# T5403_Barometer_Breakout.net
KiCad netlist of a schematic drawn in EAGLE
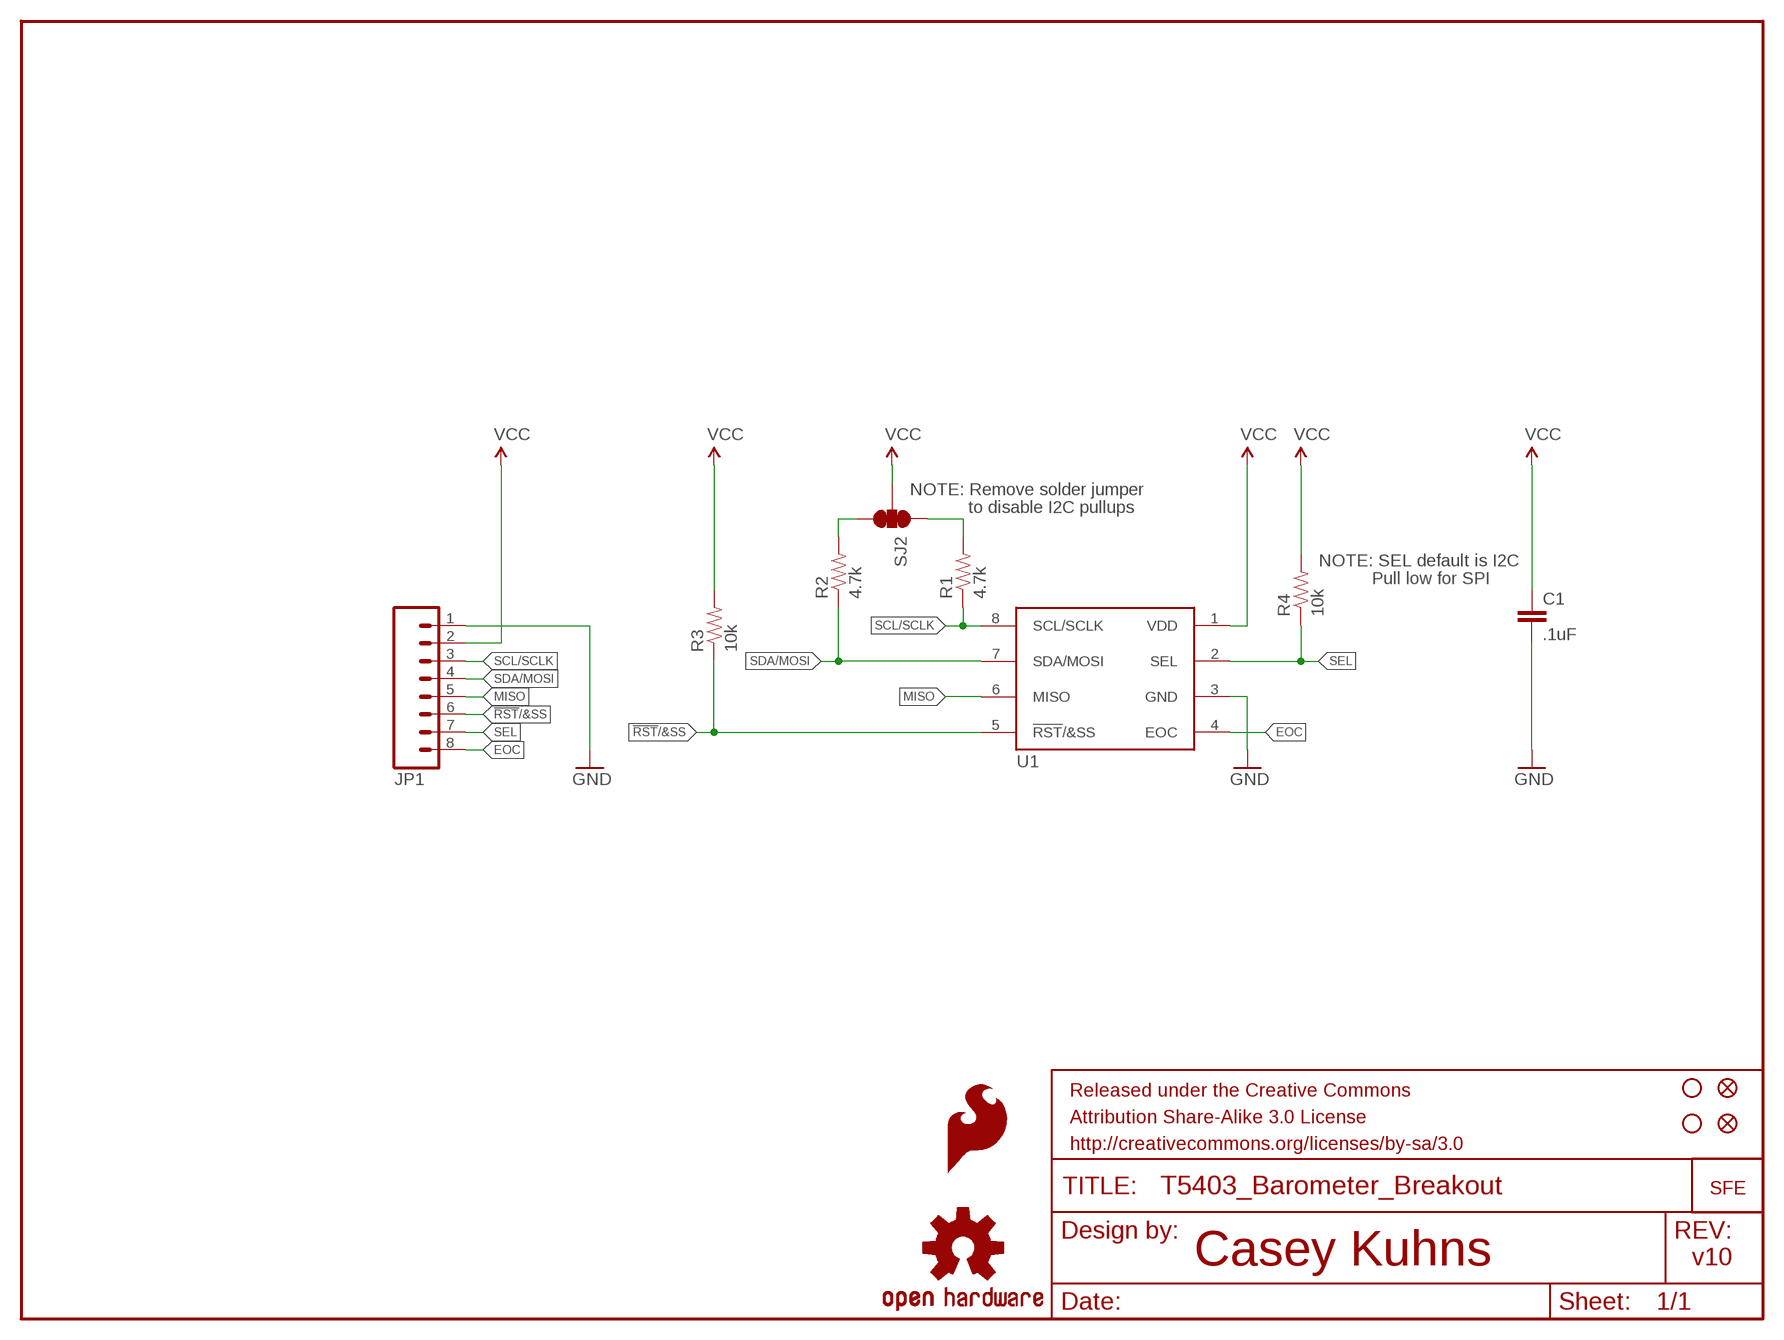
[diagram p0: schematic, sheet 1]

(export (version "E")
  (design (tool "Eeschema 10.0.6"))
  (components
    (comp (ref "C1")
      (value ".1uF")
      (footprint "eagle-import:0603-CAP")
      (libsource (lib "eagle-import") (part "0.1UF-25V-5%(0603)"))
    )
    (comp (ref "FID1")
      (value "FIDUCIAL1X2")
      (footprint "eagle-import:FIDUCIAL-1X2")
      (libsource (lib "eagle-import") (part "FIDUCIAL1X2"))
    )
    (comp (ref "FID2")
      (value "FIDUCIAL1X2")
      (footprint "eagle-import:FIDUCIAL-1X2")
      (libsource (lib "eagle-import") (part "FIDUCIAL1X2"))
    )
    (comp (ref "FRAME1")
      (value "FRAME-LETTER")
      (footprint "eagle-import:CREATIVE_COMMONS")
      (libsource (lib "eagle-import") (part "FRAME-LETTER"))
    )
    (comp (ref "JP1")
      (value "M081X08")
      (footprint "eagle-import:1X08")
      (libsource (lib "eagle-import") (part "M081X08"))
    )
    (comp (ref "LOGO1")
      (value "LOGO-SFENEW")
      (footprint "eagle-import:SFE-NEW-WEBLOGO")
      (libsource (lib "eagle-import") (part "LOGO-SFENEW"))
    )
    (comp (ref "LOGO2")
      (value "OSHW-LOGOS")
      (footprint "eagle-import:OSHW-LOGO-S")
      (libsource (lib "eagle-import") (part "OSHW-LOGOS"))
    )
    (comp (ref "LOGO3")
      (value "SFE_LOGO_FLAME.1_INCH")
      (footprint "eagle-import:SFE_LOGO_FLAME_.1")
      (libsource (lib "eagle-import") (part "SFE_LOGO_FLAME.1_INCH"))
    )
    (comp (ref "R1")
      (value "4.7k")
      (footprint "eagle-import:0603")
      (libsource (lib "eagle-import") (part "4.7KOHM1/10W1%(0603)"))
    )
    (comp (ref "R2")
      (value "4.7k")
      (footprint "eagle-import:0603")
      (libsource (lib "eagle-import") (part "4.7KOHM1/10W1%(0603)"))
    )
    (comp (ref "R3")
      (value "10k")
      (footprint "eagle-import:0603-RES")
      (libsource (lib "eagle-import") (part "10KOHM1/10W1%(0603)0603"))
    )
    (comp (ref "R4")
      (value "10k")
      (footprint "eagle-import:0603-RES")
      (libsource (lib "eagle-import") (part "10KOHM1/10W1%(0603)0603"))
    )
    (comp (ref "SJ2")
      (value "SOLDERJUMPER_2WAYPASTE1&2&3")
      (footprint "eagle-import:SJ_3_PASTE1&2&3")
      (libsource (lib "eagle-import") (part "SOLDERJUMPER_2WAYPASTE1&2&3"))
    )
    (comp (ref "STANDOFF1")
      (value "STAND-OFF")
      (footprint "eagle-import:STAND-OFF")
      (libsource (lib "eagle-import") (part "STAND-OFF"))
    )
    (comp (ref "STANDOFF2")
      (value "STAND-OFF")
      (footprint "eagle-import:STAND-OFF")
      (libsource (lib "eagle-import") (part "STAND-OFF"))
    )
    (comp (ref "U1")
      (value "T5400")
      (footprint "eagle-import:T5400")
      (libsource (lib "eagle-import") (part "T5400"))
    )
  )
  (nets
    (net (code "1") (name "/~{RST}{slash}&SS") (class "Default")
      (node (ref "JP1") (pin "6") (pinfunction "6_6") (pintype "passive"))
      (node (ref "R3") (pin "1") (pinfunction "1_1") (pintype "passive"))
      (node (ref "U1") (pin "5") (pinfunction "~{RST}/&SS_5") (pintype "bidirectional"))
    )
    (net (code "2") (name "EOC") (class "Default")
      (node (ref "JP1") (pin "8") (pinfunction "8_8") (pintype "passive"))
      (node (ref "U1") (pin "4") (pinfunction "EOC_4") (pintype "bidirectional"))
    )
    (net (code "3") (name "GND") (class "Default")
      (node (ref "C1") (pin "2") (pinfunction "2_2") (pintype "passive"))
      (node (ref "JP1") (pin "1") (pinfunction "1_1") (pintype "passive"))
      (node (ref "U1") (pin "3") (pinfunction "GND_3") (pintype "bidirectional"))
    )
    (net (code "4") (name "MISO") (class "Default")
      (node (ref "JP1") (pin "5") (pinfunction "5_5") (pintype "passive"))
      (node (ref "U1") (pin "6") (pinfunction "MISO_6") (pintype "bidirectional"))
    )
    (net (code "5") (name "Net-(R1-Pad2)") (class "Default")
      (node (ref "R1") (pin "2") (pinfunction "2_2") (pintype "passive"))
      (node (ref "SJ2") (pin "1") (pinfunction "1_1") (pintype "passive"))
    )
    (net (code "6") (name "Net-(R2-Pad2)") (class "Default")
      (node (ref "R2") (pin "2") (pinfunction "2_2") (pintype "passive"))
      (node (ref "SJ2") (pin "3") (pinfunction "3_3") (pintype "passive"))
    )
    (net (code "7") (name "SCL{slash}SCLK") (class "Default")
      (node (ref "JP1") (pin "3") (pinfunction "3_3") (pintype "passive"))
      (node (ref "R1") (pin "1") (pinfunction "1_1") (pintype "passive"))
      (node (ref "U1") (pin "8") (pinfunction "SCL/SCLK_8") (pintype "bidirectional"))
    )
    (net (code "8") (name "SDA{slash}MOSI") (class "Default")
      (node (ref "JP1") (pin "4") (pinfunction "4_4") (pintype "passive"))
      (node (ref "R2") (pin "1") (pinfunction "1_1") (pintype "passive"))
      (node (ref "U1") (pin "7") (pinfunction "SDA/MOSI_7") (pintype "bidirectional"))
    )
    (net (code "9") (name "SEL") (class "Default")
      (node (ref "JP1") (pin "7") (pinfunction "7_7") (pintype "passive"))
      (node (ref "R4") (pin "1") (pinfunction "1_1") (pintype "passive"))
      (node (ref "U1") (pin "2") (pinfunction "SEL_2") (pintype "bidirectional"))
    )
    (net (code "10") (name "VCC") (class "Default")
      (node (ref "C1") (pin "1") (pinfunction "1_1") (pintype "passive"))
      (node (ref "JP1") (pin "2") (pinfunction "2_2") (pintype "passive"))
      (node (ref "R3") (pin "2") (pinfunction "2_2") (pintype "passive"))
      (node (ref "R4") (pin "2") (pinfunction "2_2") (pintype "passive"))
      (node (ref "SJ2") (pin "2") (pinfunction "2_2") (pintype "passive"))
      (node (ref "U1") (pin "1") (pinfunction "VDD_1") (pintype "bidirectional"))
    )
  )
)
